# VREG_RT9166-18PVL_with_EN.net
KiCad netlist of a schematic drawn in Altium Designer
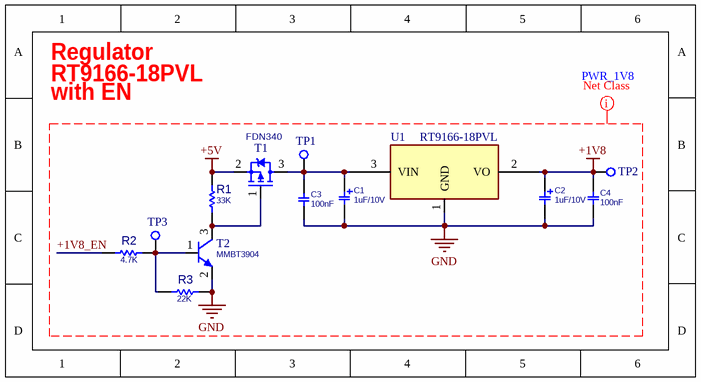
[diagram p0: VREG RT9166-18PVL with EN.SchDoc]

(export (version "E")
  (design (tool "Eeschema 10.0.6"))
  (components
    (comp (ref "C1")
      (value "1uF/10V")
      (footprint "C_TN_A")
      (description "CAP, SMD, TAN")
      (libsource (lib "PW Components 97_492") (part "CAP_SMD_TAN"))
    )
    (comp (ref "C2")
      (value "1uF/10V")
      (footprint "C_TN_A")
      (description "CAP, SMD, TAN")
      (libsource (lib "PW Components 97_492") (part "CAP_SMD_TAN"))
    )
    (comp (ref "C3")
      (value "100nF")
      (footprint "C0603S")
      (description "CAP, SMD, MLCC")
      (fields (field (name "MANF_P#") "MANF_PART#") (field (name "MANF") "Murata"))
      (libsource (lib "Passive") (part "CAP_SMD_MLCC"))
    )
    (comp (ref "C4")
      (value "100nF")
      (footprint "C0603S")
      (description "CAP, SMD, MLCC")
      (fields (field (name "MANF_P#") "MANF_PART#") (field (name "MANF") "Murata"))
      (libsource (lib "Passive") (part "CAP_SMD_MLCC"))
    )
    (comp (ref "R1")
      (value "33K")
      (footprint "R0603S")
      (description "RES, SMD")
      (fields (field (name "MANF_P#") "RK73H1ETTP4701F") (field (name "MANF") "KOA SPEER"))
      (libsource (lib "Passive") (part "RES_SMD"))
    )
    (comp (ref "R2")
      (value "4.7K")
      (footprint "R0603S")
      (description "RES, SMD")
      (fields (field (name "MANF_P#") "RK73H1ETTP4701F") (field (name "MANF") "KOA SPEER"))
      (libsource (lib "Passive") (part "RES_SMD"))
    )
    (comp (ref "R3")
      (value "22K")
      (footprint "R0603S")
      (description "RES, SMD")
      (fields (field (name "MANF_P#") "RK73H1ETTP4701F") (field (name "MANF") "KOA SPEER"))
      (libsource (lib "Passive") (part "RES_SMD"))
    )
    (comp (ref "T1")
      (value "FDN340")
      (footprint "SOT23_3")
      (description "MOSFET SMD P-CH 20V 2A")
      (fields (field (name "MANF_P#") "FDN360"))
      (libsource (lib "Transistor FET") (part "MOSP_FDN340_SOT23"))
    )
    (comp (ref "T2")
      (value "MMBT3904")
      (footprint "SOT23_3")
      (description "BJT, NPN, 40V, 0.2A, SMD, SOT23")
      (fields (field (name "MANF") "Diodes, NXP, FAIRCHILD, ON"))
      (libsource (lib "Transistor BJT") (part "NPN_MMBT3904_SOT23"))
    )
    (comp (ref "TP1")
      (value "Test Point")
      (footprint "TPSMD_C1")
      (libsource (lib "Passives") (part "Test Point"))
    )
    (comp (ref "TP2")
      (value "Test Point")
      (footprint "TPSMD_C1")
      (libsource (lib "Passives") (part "Test Point"))
    )
    (comp (ref "TP3")
      (value "Test Point")
      (footprint "TPSMD_C1")
      (libsource (lib "Passives") (part "Test Point"))
    )
    (comp (ref "U1")
      (value "RT9166-18PVL")
      (footprint "SOT23_3")
      (description "REG, Linear, Fixed, 1.8v, 0.3A/0.6A, SOT23")
      (fields (field (name "MANF") "TI"))
      (libsource (lib "PW Components 97_481") (part "VREG_RT9166A-18PVL_SOT23"))
    )
  )
  (nets
    (net (code "1") (name "+1V8") (class "Default")
      (node (ref "C2") (pin "1") (pinfunction "1_1") (pintype "passive"))
      (node (ref "C4") (pin "1") (pinfunction "1_1") (pintype "passive"))
      (node (ref "TP2") (pin "1") (pinfunction "TP_1") (pintype "passive"))
      (node (ref "U1") (pin "2") (pinfunction "VO_2") (pintype "passive"))
    )
    (net (code "2") (name "+5V") (class "Default")
      (node (ref "R1") (pin "2") (pinfunction "2_2") (pintype "passive"))
      (node (ref "T1") (pin "2") (pinfunction "S_2") (pintype "passive"))
    )
    (net (code "3") (name "/+1V8_EN") (class "Default")
      (node (ref "R2") (pin "2") (pinfunction "2_2") (pintype "passive"))
    )
    (net (code "4") (name "GND") (class "Default")
      (node (ref "C1") (pin "2") (pinfunction "2_2") (pintype "passive"))
      (node (ref "C2") (pin "2") (pinfunction "2_2") (pintype "passive"))
      (node (ref "C3") (pin "2") (pinfunction "2_2") (pintype "passive"))
      (node (ref "C4") (pin "2") (pinfunction "2_2") (pintype "passive"))
      (node (ref "R3") (pin "1") (pinfunction "1_1") (pintype "passive"))
      (node (ref "T2") (pin "2") (pinfunction "E_2") (pintype "passive"))
      (node (ref "U1") (pin "1") (pinfunction "GND_1") (pintype "passive"))
    )
    (net (code "5") (name "Net-(T1-D)") (class "Default")
      (node (ref "C1") (pin "1") (pinfunction "1_1") (pintype "passive"))
      (node (ref "C3") (pin "1") (pinfunction "1_1") (pintype "passive"))
      (node (ref "T1") (pin "3") (pinfunction "D_3") (pintype "passive"))
      (node (ref "TP1") (pin "1") (pinfunction "TP_1") (pintype "passive"))
      (node (ref "U1") (pin "3") (pinfunction "VIN_3") (pintype "passive"))
    )
    (net (code "6") (name "Net-(T1-G)") (class "Default")
      (node (ref "R1") (pin "1") (pinfunction "1_1") (pintype "passive"))
      (node (ref "T1") (pin "1") (pinfunction "G_1") (pintype "passive"))
      (node (ref "T2") (pin "3") (pinfunction "C_3") (pintype "passive"))
    )
    (net (code "7") (name "Net-(T2-B)") (class "Default")
      (node (ref "R2") (pin "1") (pinfunction "1_1") (pintype "passive"))
      (node (ref "R3") (pin "2") (pinfunction "2_2") (pintype "passive"))
      (node (ref "T2") (pin "1") (pinfunction "B_1") (pintype "passive"))
      (node (ref "TP3") (pin "1") (pinfunction "TP_1") (pintype "passive"))
    )
  )
)
